# OpenLog.net
KiCad netlist of a schematic drawn in EAGLE
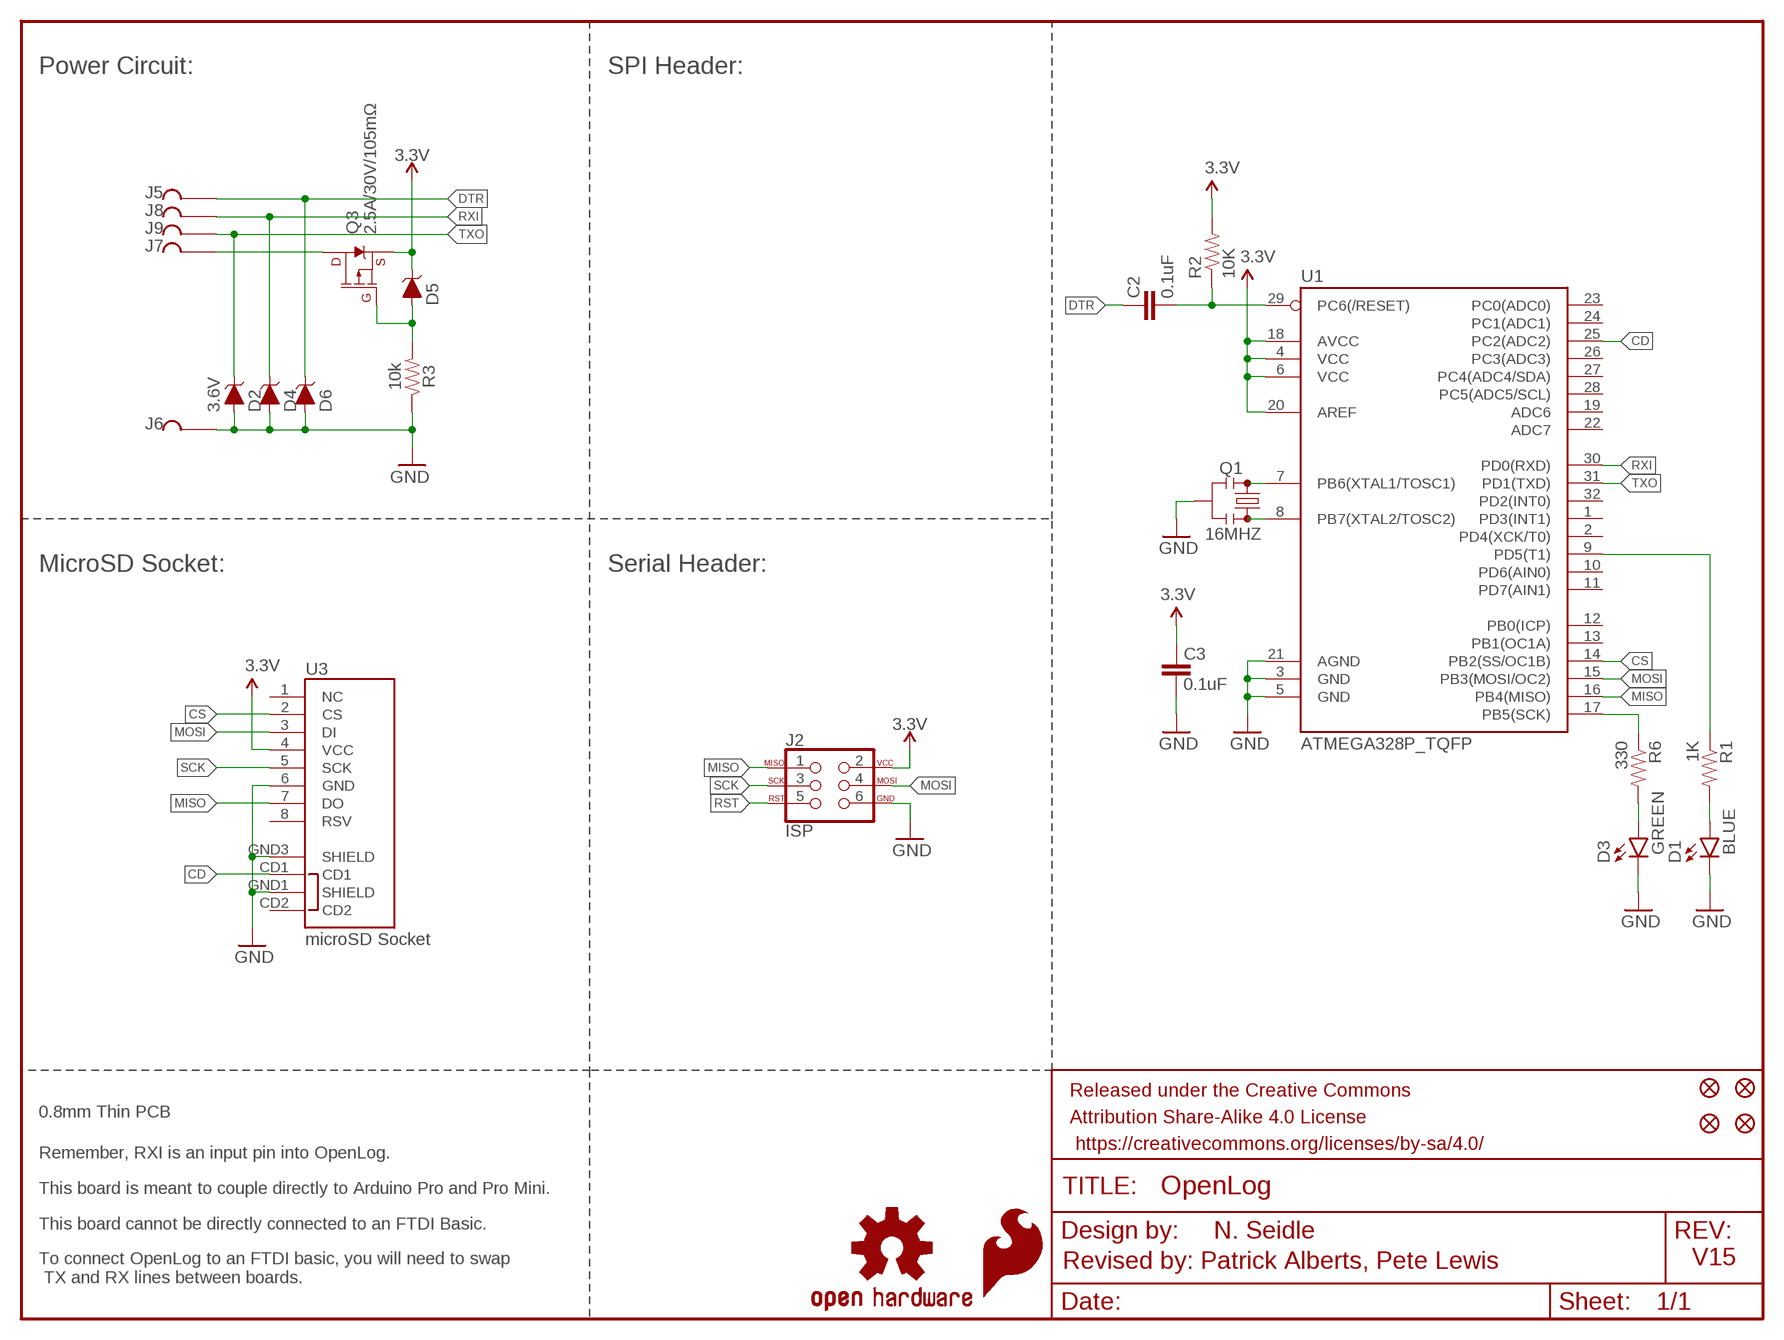
[diagram p0: schematic, sheet 1]

(export (version "E")
  (design (tool "Eeschema 10.0.6"))
  (components
    (comp (ref "C2")
      (value "0.1uF")
      (footprint "eagle-import:0603-CAP")
      (libsource (lib "eagle-import") (part "0.1UF-25V(+80/-20%)(0603)"))
    )
    (comp (ref "C3")
      (value "0.1uF")
      (footprint "eagle-import:0603-CAP")
      (libsource (lib "eagle-import") (part "0.1UF-25V(+80/-20%)(0603)"))
    )
    (comp (ref "D1")
      (value "BLUE")
      (footprint "eagle-import:LED-0603")
      (libsource (lib "eagle-import") (part "LED-BLUE0603"))
    )
    (comp (ref "D2")
      (value "3.6V")
      (footprint "eagle-import:SOD-323")
      (libsource (lib "eagle-import") (part "DIODE-ZENER-BZT52C3V6S"))
    )
    (comp (ref "D3")
      (value "GREEN")
      (footprint "eagle-import:LED-0603")
      (libsource (lib "eagle-import") (part "LED-GREEN0603"))
    )
    (comp (ref "D4")
      (value "3.6V")
      (footprint "eagle-import:SOD-323")
      (libsource (lib "eagle-import") (part "DIODE-ZENER-BZT52C3V6S"))
    )
    (comp (ref "D5")
      (value "3.6V")
      (footprint "eagle-import:SOD-323")
      (libsource (lib "eagle-import") (part "DIODE-ZENER-BZT52C3V6S"))
    )
    (comp (ref "D6")
      (value "3.6V")
      (footprint "eagle-import:SOD-323")
      (libsource (lib "eagle-import") (part "DIODE-ZENER-BZT52C3V6S"))
    )
    (comp (ref "FID1")
      (value "FIDUCIALUFIDUCIAL")
      (footprint "eagle-import:FIDUCIAL-MICRO")
      (libsource (lib "eagle-import") (part "FIDUCIALUFIDUCIAL"))
    )
    (comp (ref "FID2")
      (value "FIDUCIALUFIDUCIAL")
      (footprint "eagle-import:FIDUCIAL-MICRO")
      (libsource (lib "eagle-import") (part "FIDUCIALUFIDUCIAL"))
    )
    (comp (ref "FID3")
      (value "FIDUCIALUFIDUCIAL")
      (footprint "eagle-import:FIDUCIAL-MICRO")
      (libsource (lib "eagle-import") (part "FIDUCIALUFIDUCIAL"))
    )
    (comp (ref "FID4")
      (value "FIDUCIALUFIDUCIAL")
      (footprint "eagle-import:FIDUCIAL-MICRO")
      (libsource (lib "eagle-import") (part "FIDUCIALUFIDUCIAL"))
    )
    (comp (ref "FRAME1")
      (value "FRAME-LETTER")
      (footprint "eagle-import:CREATIVE_COMMONS")
      (libsource (lib "eagle-import") (part "FRAME-LETTER"))
    )
    (comp (ref "J2")
      (value "ISP")
      (footprint "eagle-import:2X3_TEST_POINTS")
      (libsource (lib "eagle-import") (part "AVR_SPI_PROG_3X2TESTPOINTS"))
    )
    (comp (ref "J5")
      (value "GATORGATOR_MINI")
      (footprint "eagle-import:GATOR_MINI")
      (libsource (lib "eagle-import") (part "GATORGATOR_MINI"))
    )
    (comp (ref "J6")
      (value "GATORGATOR_MINI")
      (footprint "eagle-import:GATOR_MINI")
      (libsource (lib "eagle-import") (part "GATORGATOR_MINI"))
    )
    (comp (ref "J7")
      (value "GATORGATOR_MINI")
      (footprint "eagle-import:GATOR_MINI")
      (libsource (lib "eagle-import") (part "GATORGATOR_MINI"))
    )
    (comp (ref "J8")
      (value "GATORGATOR_MINI")
      (footprint "eagle-import:GATOR_MINI")
      (libsource (lib "eagle-import") (part "GATORGATOR_MINI"))
    )
    (comp (ref "J9")
      (value "GATORGATOR_MINI")
      (footprint "eagle-import:GATOR_MINI")
      (libsource (lib "eagle-import") (part "GATORGATOR_MINI"))
    )
    (comp (ref "LOGO1")
      (value "SFE_LOGO_FLAME.1_INCH")
      (footprint "eagle-import:SFE_LOGO_FLAME_.1")
      (libsource (lib "eagle-import") (part "SFE_LOGO_FLAME.1_INCH"))
    )
    (comp (ref "LOGO2")
      (value "OSHW-LOGOMINI")
      (footprint "eagle-import:OSHW-LOGO-MINI")
      (libsource (lib "eagle-import") (part "OSHW-LOGOMINI"))
    )
    (comp (ref "Q1")
      (value "16MHZ")
      (footprint "eagle-import:RESONATOR-SMD")
      (libsource (lib "eagle-import") (part "RESONATOR16MHZ"))
    )
    (comp (ref "Q3")
      (value "2.5A/30V/105mΩ")
      (footprint "eagle-import:SOT23-3")
      (libsource (lib "eagle-import") (part "MOSFET_PCH-DMG2307L"))
    )
    (comp (ref "R1")
      (value "1K")
      (footprint "eagle-import:0603-RES")
      (libsource (lib "eagle-import") (part "1KOHM-1/10W-1%(0603)"))
    )
    (comp (ref "R2")
      (value "10K")
      (footprint "eagle-import:0603-RES")
      (libsource (lib "eagle-import") (part "10KOHM-1/10W-1%(0603)0603"))
    )
    (comp (ref "R3")
      (value "10k")
      (footprint "eagle-import:0603")
      (libsource (lib "eagle-import") (part "10KOHM-0603-1/10W-1%"))
    )
    (comp (ref "R6")
      (value "330")
      (footprint "eagle-import:0603-RES")
      (libsource (lib "eagle-import") (part "330OHM1/10W1%(0603)"))
    )
    (comp (ref "U1")
      (value "ATMEGA328P_TQFP")
      (footprint "eagle-import:TQFP32-08")
      (libsource (lib "eagle-import") (part "ATMEGA328P_TQFP"))
    )
    (comp (ref "U3")
      (value "microSD Socket")
      (footprint "eagle-import:MICROSD_1_1")
      (libsource (lib "eagle-import") (part "USD-SOCKET"))
    )
  )
  (nets
    (net (code "1") (name "3.3V") (class "Default")
      (node (ref "C3") (pin "2") (pinfunction "2_2") (pintype "passive"))
      (node (ref "D5") (pin "C") (pinfunction "C_C") (pintype "passive"))
      (node (ref "J2") (pin "2") (pinfunction "2_2") (pintype "passive"))
      (node (ref "Q3") (pin "2") (pinfunction "S_2") (pintype "bidirectional"))
      (node (ref "R2") (pin "2") (pinfunction "2_2") (pintype "passive"))
      (node (ref "U1") (pin "18") (pinfunction "AVCC_18") (pintype "bidirectional"))
      (node (ref "U1") (pin "20") (pinfunction "AREF_20") (pintype "bidirectional"))
      (node (ref "U1") (pin "4") (pinfunction "VCC_4") (pintype "bidirectional"))
      (node (ref "U1") (pin "6") (pinfunction "VCC_6") (pintype "bidirectional"))
      (node (ref "U3") (pin "4") (pinfunction "VCC_4") (pintype "bidirectional"))
    )
    (net (code "2") (name "CD") (class "Default")
      (node (ref "U1") (pin "25") (pinfunction "PC2(ADC2)_25") (pintype "bidirectional"))
      (node (ref "U3") (pin "CD1") (pinfunction "CD1_CD1") (pintype "bidirectional"))
    )
    (net (code "3") (name "CS") (class "Default")
      (node (ref "U1") (pin "14") (pinfunction "PB2(SS/OC1B)_14") (pintype "bidirectional"))
      (node (ref "U3") (pin "2") (pinfunction "CS_2") (pintype "bidirectional"))
    )
    (net (code "4") (name "DTR") (class "Default")
      (node (ref "C2") (pin "2") (pinfunction "2_2") (pintype "passive"))
      (node (ref "D6") (pin "C") (pinfunction "C_C") (pintype "passive"))
      (node (ref "J5") (pin "P$2") (pinfunction "P$1_P$2") (pintype "bidirectional"))
    )
    (net (code "5") (name "GND") (class "Default")
      (node (ref "C3") (pin "1") (pinfunction "1_1") (pintype "passive"))
      (node (ref "D1") (pin "C") (pinfunction "C_C") (pintype "passive"))
      (node (ref "D2") (pin "A") (pinfunction "A_A") (pintype "passive"))
      (node (ref "D3") (pin "C") (pinfunction "C_C") (pintype "passive"))
      (node (ref "D4") (pin "A") (pinfunction "A_A") (pintype "passive"))
      (node (ref "D6") (pin "A") (pinfunction "A_A") (pintype "passive"))
      (node (ref "J2") (pin "6") (pinfunction "6_6") (pintype "passive"))
      (node (ref "J6") (pin "P$2") (pinfunction "P$1_P$2") (pintype "bidirectional"))
      (node (ref "Q1") (pin "2") (pinfunction "2_2") (pintype "passive"))
      (node (ref "R3") (pin "1") (pinfunction "1_1") (pintype "passive"))
      (node (ref "U1") (pin "21") (pinfunction "AGND_21") (pintype "bidirectional"))
      (node (ref "U1") (pin "3") (pinfunction "GND_3") (pintype "bidirectional"))
      (node (ref "U1") (pin "5") (pinfunction "GND_5") (pintype "bidirectional"))
      (node (ref "U3") (pin "6") (pinfunction "GND_6") (pintype "bidirectional"))
      (node (ref "U3") (pin "GND1") (pinfunction "SHIELD_GND1") (pintype "bidirectional"))
      (node (ref "U3") (pin "GND3") (pinfunction "SHIELD_GND3") (pintype "bidirectional"))
    )
    (net (code "6") (name "MISO") (class "Default")
      (node (ref "J2") (pin "1") (pinfunction "1_1") (pintype "passive"))
      (node (ref "U1") (pin "16") (pinfunction "PB4(MISO)_16") (pintype "bidirectional"))
      (node (ref "U3") (pin "7") (pinfunction "DO_7") (pintype "bidirectional"))
    )
    (net (code "7") (name "MOSI") (class "Default")
      (node (ref "J2") (pin "4") (pinfunction "4_4") (pintype "passive"))
      (node (ref "U1") (pin "15") (pinfunction "PB3(MOSI/OC2)_15") (pintype "bidirectional"))
      (node (ref "U3") (pin "3") (pinfunction "DI_3") (pintype "bidirectional"))
    )
    (net (code "8") (name "Net-(D1-PadA)") (class "Default")
      (node (ref "D1") (pin "A") (pinfunction "A_A") (pintype "passive"))
      (node (ref "R1") (pin "2") (pinfunction "2_2") (pintype "passive"))
    )
    (net (code "9") (name "Net-(D3-PadA)") (class "Default")
      (node (ref "D3") (pin "A") (pinfunction "A_A") (pintype "passive"))
      (node (ref "R6") (pin "2") (pinfunction "2_2") (pintype "passive"))
    )
    (net (code "10") (name "Net-(J7-P$1)") (class "Default")
      (node (ref "J7") (pin "P$2") (pinfunction "P$1_P$2") (pintype "bidirectional"))
      (node (ref "Q3") (pin "3") (pinfunction "D_3") (pintype "bidirectional"))
    )
    (net (code "11") (name "Net-(Q3-G)") (class "Default")
      (node (ref "D5") (pin "A") (pinfunction "A_A") (pintype "passive"))
      (node (ref "Q3") (pin "1") (pinfunction "G_1") (pintype "bidirectional"))
      (node (ref "R3") (pin "2") (pinfunction "2_2") (pintype "passive"))
    )
    (net (code "12") (name "Net-(U1-PB6(XTAL1{slash}TOSC1))") (class "Default")
      (node (ref "Q1") (pin "3") (pinfunction "3_3") (pintype "passive"))
      (node (ref "U1") (pin "7") (pinfunction "PB6(XTAL1/TOSC1)_7") (pintype "bidirectional"))
    )
    (net (code "13") (name "Net-(U1-PB7(XTAL2{slash}TOSC2))") (class "Default")
      (node (ref "Q1") (pin "1") (pinfunction "1_1") (pintype "passive"))
      (node (ref "U1") (pin "8") (pinfunction "PB7(XTAL2/TOSC2)_8") (pintype "bidirectional"))
    )
    (net (code "14") (name "Net-(U1-PD5(T1))") (class "Default")
      (node (ref "R1") (pin "1") (pinfunction "1_1") (pintype "passive"))
      (node (ref "U1") (pin "9") (pinfunction "PD5(T1)_9") (pintype "bidirectional"))
    )
    (net (code "15") (name "RST") (class "Default")
      (node (ref "C2") (pin "1") (pinfunction "1_1") (pintype "passive"))
      (node (ref "J2") (pin "5") (pinfunction "5_5") (pintype "passive"))
      (node (ref "R2") (pin "1") (pinfunction "1_1") (pintype "passive"))
      (node (ref "U1") (pin "29") (pinfunction "PC6(/RESET)_29") (pintype "bidirectional"))
    )
    (net (code "16") (name "RXI") (class "Default")
      (node (ref "D4") (pin "C") (pinfunction "C_C") (pintype "passive"))
      (node (ref "J8") (pin "P$2") (pinfunction "P$1_P$2") (pintype "bidirectional"))
      (node (ref "U1") (pin "30") (pinfunction "PD0(RXD)_30") (pintype "bidirectional"))
    )
    (net (code "17") (name "SCK") (class "Default")
      (node (ref "J2") (pin "3") (pinfunction "3_3") (pintype "passive"))
      (node (ref "R6") (pin "1") (pinfunction "1_1") (pintype "passive"))
      (node (ref "U1") (pin "17") (pinfunction "PB5(SCK)_17") (pintype "bidirectional"))
      (node (ref "U3") (pin "5") (pinfunction "SCK_5") (pintype "bidirectional"))
    )
    (net (code "18") (name "TXO") (class "Default")
      (node (ref "D2") (pin "C") (pinfunction "C_C") (pintype "passive"))
      (node (ref "J9") (pin "P$2") (pinfunction "P$1_P$2") (pintype "bidirectional"))
      (node (ref "U1") (pin "31") (pinfunction "PD1(TXD)_31") (pintype "bidirectional"))
    )
    (net (code "19") (name "unconnected-(U1-ADC6-Pad19)") (class "Default")
      (node (ref "U1") (pin "19") (pinfunction "ADC6_19") (pintype "bidirectional"))
    )
    (net (code "20") (name "unconnected-(U1-ADC7-Pad22)") (class "Default")
      (node (ref "U1") (pin "22") (pinfunction "ADC7_22") (pintype "bidirectional"))
    )
    (net (code "21") (name "unconnected-(U1-PB0(ICP)-Pad12)") (class "Default")
      (node (ref "U1") (pin "12") (pinfunction "PB0(ICP)_12") (pintype "bidirectional"))
    )
    (net (code "22") (name "unconnected-(U1-PB1(OC1A)-Pad13)") (class "Default")
      (node (ref "U1") (pin "13") (pinfunction "PB1(OC1A)_13") (pintype "bidirectional"))
    )
    (net (code "23") (name "unconnected-(U1-PC0(ADC0)-Pad23)") (class "Default")
      (node (ref "U1") (pin "23") (pinfunction "PC0(ADC0)_23") (pintype "bidirectional"))
    )
    (net (code "24") (name "unconnected-(U1-PC1(ADC1)-Pad24)") (class "Default")
      (node (ref "U1") (pin "24") (pinfunction "PC1(ADC1)_24") (pintype "bidirectional"))
    )
    (net (code "25") (name "unconnected-(U1-PC3(ADC3)-Pad26)") (class "Default")
      (node (ref "U1") (pin "26") (pinfunction "PC3(ADC3)_26") (pintype "bidirectional"))
    )
    (net (code "26") (name "unconnected-(U1-PC4(ADC4{slash}SDA)-Pad27)") (class "Default")
      (node (ref "U1") (pin "27") (pinfunction "PC4(ADC4/SDA)_27") (pintype "bidirectional"))
    )
    (net (code "27") (name "unconnected-(U1-PC5(ADC5{slash}SCL)-Pad28)") (class "Default")
      (node (ref "U1") (pin "28") (pinfunction "PC5(ADC5/SCL)_28") (pintype "bidirectional"))
    )
    (net (code "28") (name "unconnected-(U1-PD2(INT0)-Pad32)") (class "Default")
      (node (ref "U1") (pin "32") (pinfunction "PD2(INT0)_32") (pintype "bidirectional"))
    )
    (net (code "29") (name "unconnected-(U1-PD3(INT1)-Pad1)") (class "Default")
      (node (ref "U1") (pin "1") (pinfunction "PD3(INT1)_1") (pintype "bidirectional"))
    )
    (net (code "30") (name "unconnected-(U1-PD4(XCK{slash}T0)-Pad2)") (class "Default")
      (node (ref "U1") (pin "2") (pinfunction "PD4(XCK/T0)_2") (pintype "bidirectional"))
    )
    (net (code "31") (name "unconnected-(U1-PD6(AIN0)-Pad10)") (class "Default")
      (node (ref "U1") (pin "10") (pinfunction "PD6(AIN0)_10") (pintype "bidirectional"))
    )
    (net (code "32") (name "unconnected-(U1-PD7(AIN1)-Pad11)") (class "Default")
      (node (ref "U1") (pin "11") (pinfunction "PD7(AIN1)_11") (pintype "bidirectional"))
    )
    (net (code "33") (name "unconnected-(U3-NC-Pad1)") (class "Default")
      (node (ref "U3") (pin "1") (pinfunction "NC_1") (pintype "bidirectional"))
    )
    (net (code "34") (name "unconnected-(U3-PadCD2)") (class "Default")
      (node (ref "U3") (pin "CD2") (pinfunction "CD2_CD2") (pintype "bidirectional"))
    )
    (net (code "35") (name "unconnected-(U3-RSV-Pad8)") (class "Default")
      (node (ref "U3") (pin "8") (pinfunction "RSV_8") (pintype "bidirectional"))
    )
  )
)
